# LabPower-power.net
KiCad netlist of a schematic drawn in EAGLE
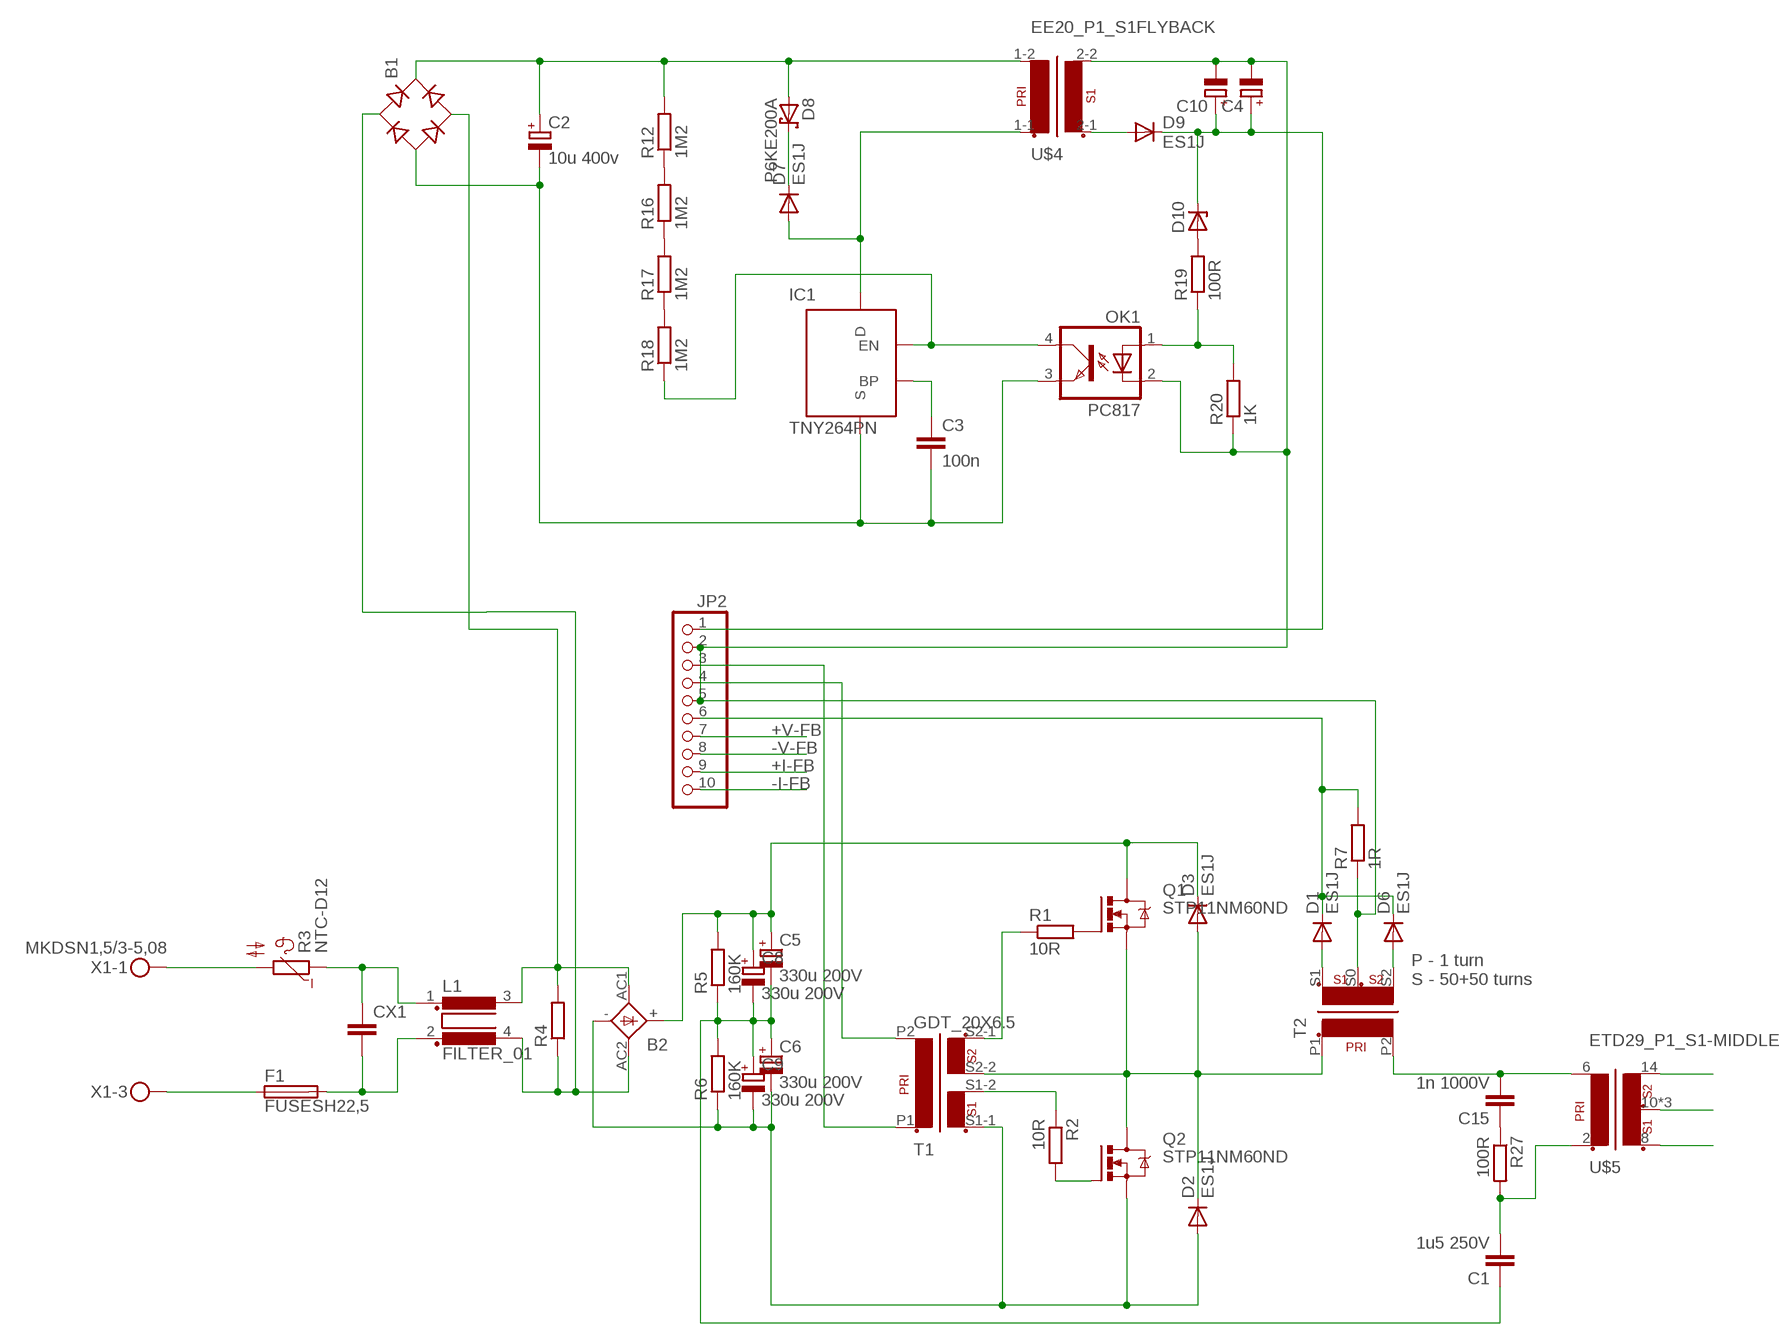
[diagram p0: schematic, sheet 1]
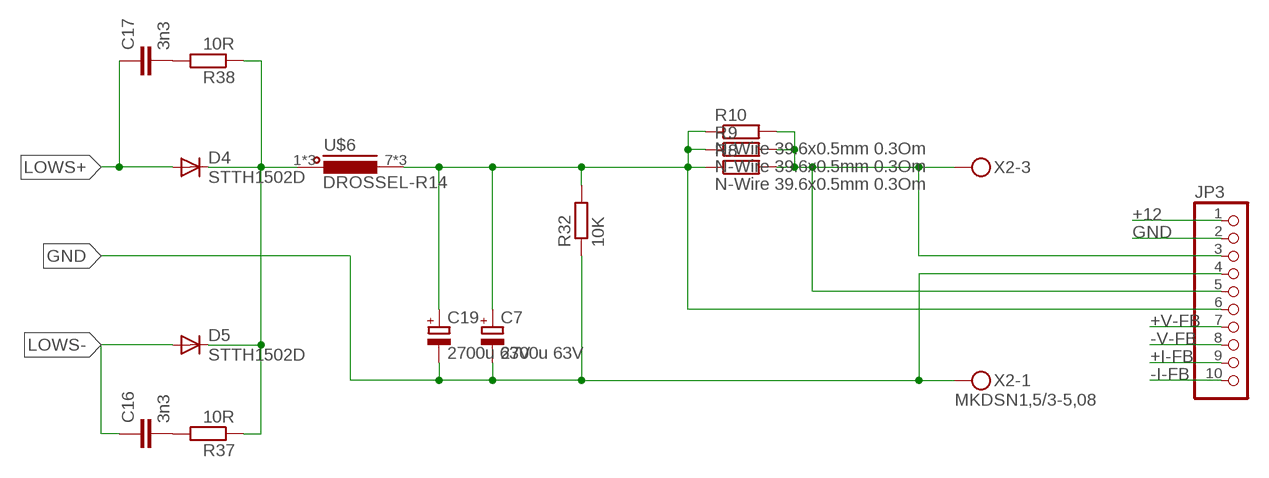
[diagram p1: schematic, sheet 2]

(export (version "E")
  (design (tool "Eeschema 10.0.6"))
  (components
    (comp (ref "B1")
      (value "RB1A")
      (footprint "eagle-import:RB1A")
      (libsource (lib "eagle-import") (part "RB1A"))
    )
    (comp (ref "B2")
      (value "KBL")
      (footprint "eagle-import:KBL")
      (libsource (lib "eagle-import") (part "KBL"))
    )
    (comp (ref "C1")
      (value "1u5 250V")
      (footprint "eagle-import:C225-074X268")
      (libsource (lib "eagle-import") (part "C-EU225-074X268"))
    )
    (comp (ref "C2")
      (value "10u 400v")
      (footprint "eagle-import:E5-13")
      (libsource (lib "eagle-import") (part "CPOL-EUE5-13"))
    )
    (comp (ref "C3")
      (value "100n")
      (footprint "eagle-import:C0805")
      (libsource (lib "eagle-import") (part "C-EUC0805"))
    )
    (comp (ref "C4")
      (value "CPOL-EUE2.5-7")
      (footprint "eagle-import:E2,5-7")
      (libsource (lib "eagle-import") (part "CPOL-EUE2.5-7"))
    )
    (comp (ref "C5")
      (value "330u 200V")
      (footprint "eagle-import:EB22,5D")
      (libsource (lib "eagle-import") (part "CPOL-EUE10-22.5"))
    )
    (comp (ref "C6")
      (value "330u 200V")
      (footprint "eagle-import:EB22,5D")
      (libsource (lib "eagle-import") (part "CPOL-EUE10-22.5"))
    )
    (comp (ref "C8")
      (value "330u 200V")
      (footprint "eagle-import:EB22,5D")
      (libsource (lib "eagle-import") (part "CPOL-EUE10-22.5"))
    )
    (comp (ref "C9")
      (value "330u 200V")
      (footprint "eagle-import:EB22,5D")
      (libsource (lib "eagle-import") (part "CPOL-EUE10-22.5"))
    )
    (comp (ref "C10")
      (value "CPOL-EUE2.5-7")
      (footprint "eagle-import:E2,5-7")
      (libsource (lib "eagle-import") (part "CPOL-EUE2.5-7"))
    )
    (comp (ref "C15")
      (value "1n 1000V")
      (footprint "eagle-import:C050-025X075")
      (libsource (lib "eagle-import") (part "C-EU050-025X075"))
    )
    (comp (ref "CX1")
      (value "CXXC15B8")
      (footprint "eagle-import:XC15B8")
      (libsource (lib "eagle-import") (part "CXXC15B8"))
    )
    (comp (ref "D1")
      (value "ES1J")
      (footprint "eagle-import:DO214AC")
      (libsource (lib "eagle-import") (part "DIODE-DO214AC"))
    )
    (comp (ref "D2")
      (value "ES1J")
      (footprint "eagle-import:DO214AC")
      (libsource (lib "eagle-import") (part "DIODE-DO214AC"))
    )
    (comp (ref "D3")
      (value "ES1J")
      (footprint "eagle-import:DO214AC")
      (libsource (lib "eagle-import") (part "DIODE-DO214AC"))
    )
    (comp (ref "D6")
      (value "ES1J")
      (footprint "eagle-import:DO214AC")
      (libsource (lib "eagle-import") (part "DIODE-DO214AC"))
    )
    (comp (ref "D7")
      (value "ES1J")
      (footprint "eagle-import:DO214AC")
      (libsource (lib "eagle-import") (part "DIODE-DO214AC"))
    )
    (comp (ref "D8")
      (value "P6KE200A")
      (footprint "eagle-import:CB417-15")
      (libsource (lib "eagle-import") (part "P6KEXX"))
    )
    (comp (ref "D9")
      (value "ES1J")
      (footprint "eagle-import:DO214AC")
      (libsource (lib "eagle-import") (part "DIODE-DO214AC"))
    )
    (comp (ref "D10")
      (value "ZENER-DIODEDO41Z10")
      (footprint "eagle-import:DO41Z10")
      (libsource (lib "eagle-import") (part "ZENER-DIODEDO41Z10"))
    )
    (comp (ref "F1")
      (value "FUSESH22,5")
      (footprint "eagle-import:SH22,5")
      (libsource (lib "eagle-import") (part "FUSESH22,5"))
    )
    (comp (ref "IC1")
      (value "TNY264PN")
      (footprint "eagle-import:DIP-8B")
      (libsource (lib "eagle-import") (part "TNY264PN"))
    )
    (comp (ref "JP2")
      (value "PINHD-1X10")
      (footprint "eagle-import:1X10")
      (libsource (lib "eagle-import") (part "PINHD-1X10"))
    )
    (comp (ref "L1")
      (value "FILTER_01")
      (footprint "eagle-import:82721K")
      (libsource (lib "eagle-import") (part "FILTER_01"))
    )
    (comp (ref "OK1")
      (value "PC817")
      (footprint "eagle-import:DIL04")
      (fields (field (name "MPN") "PC817X4J000F"))
      (libsource (lib "eagle-import") (part "PC817"))
    )
    (comp (ref "Q1")
      (value "STP11NM60ND")
      (footprint "eagle-import:TO220BV")
      (libsource (lib "eagle-import") (part "IRF740"))
    )
    (comp (ref "Q2")
      (value "STP11NM60ND")
      (footprint "eagle-import:TO220BV")
      (libsource (lib "eagle-import") (part "IRF740"))
    )
    (comp (ref "R1")
      (value "10R")
      (footprint "eagle-import:R0805")
      (libsource (lib "eagle-import") (part "R-EU_R0805"))
    )
    (comp (ref "R2")
      (value "10R")
      (footprint "eagle-import:R0805")
      (libsource (lib "eagle-import") (part "R-EU_R0805"))
    )
    (comp (ref "R3")
      (value "NTC-D12")
      (footprint "eagle-import:NTC-D12")
      (libsource (lib "eagle-import") (part "NTC-D12"))
    )
    (comp (ref "R4")
      (value "R-EU_0309/10")
      (footprint "eagle-import:0309_10")
      (libsource (lib "eagle-import") (part "R-EU_0309/10"))
    )
    (comp (ref "R5")
      (value "160K")
      (footprint "eagle-import:0207_12")
      (libsource (lib "eagle-import") (part "R-EU_0207/12"))
    )
    (comp (ref "R6")
      (value "160K")
      (footprint "eagle-import:0207_12")
      (libsource (lib "eagle-import") (part "R-EU_0207/12"))
    )
    (comp (ref "R7")
      (value "1R")
      (footprint "eagle-import:R1206")
      (libsource (lib "eagle-import") (part "R-EU_R1206"))
    )
    (comp (ref "R12")
      (value "1M2")
      (footprint "eagle-import:R0805")
      (libsource (lib "eagle-import") (part "R-EU_R0805"))
    )
    (comp (ref "R16")
      (value "1M2")
      (footprint "eagle-import:R0805")
      (libsource (lib "eagle-import") (part "R-EU_R0805"))
    )
    (comp (ref "R17")
      (value "1M2")
      (footprint "eagle-import:R0805")
      (libsource (lib "eagle-import") (part "R-EU_R0805"))
    )
    (comp (ref "R18")
      (value "1M2")
      (footprint "eagle-import:R0805")
      (libsource (lib "eagle-import") (part "R-EU_R0805"))
    )
    (comp (ref "R19")
      (value "100R")
      (footprint "eagle-import:R0805")
      (libsource (lib "eagle-import") (part "R-EU_R0805"))
    )
    (comp (ref "R20")
      (value "1K")
      (footprint "eagle-import:R0805")
      (libsource (lib "eagle-import") (part "R-EU_R0805"))
    )
    (comp (ref "R27")
      (value "100R")
      (footprint "eagle-import:0617_17")
      (libsource (lib "eagle-import") (part "R-EU_0617/17"))
    )
    (comp (ref "T1")
      (value "GDT_20X6.5")
      (footprint "eagle-import:GDT_20X6.5")
      (libsource (lib "eagle-import") (part "GDT_20X6.5"))
    )
    (comp (ref "T2")
      (value "CURRENT")
      (footprint "eagle-import:T_10X6X3")
      (libsource (lib "eagle-import") (part "CURRENT"))
    )
    (comp (ref "U$4")
      (value "EE20_P1_S1FLYBACK")
      (footprint "eagle-import:EE20_P1_S1-REV-4PIN")
      (libsource (lib "eagle-import") (part "EE20_P1_S1FLYBACK"))
    )
    (comp (ref "U$5")
      (value "ETD29_P1_S1-MIDDLE")
      (footprint "eagle-import:ETD29")
      (libsource (lib "eagle-import") (part "ETD29_P1_S1-MIDDLE"))
    )
    (comp (ref "X1")
      (value "MKDSN1,5/3-5,08")
      (footprint "eagle-import:MKDSN1,5_3-5,08")
      (libsource (lib "eagle-import") (part "MKDSN1,5/3-5,08"))
    )
    (comp (ref "C7")
      (value "2700u 63V")
      (footprint "eagle-import:E7,5-18")
      (libsource (lib "eagle-import") (part "CPOL-EUE7.5-18"))
    )
    (comp (ref "C16")
      (value "3n3")
      (footprint "eagle-import:C0805")
      (libsource (lib "eagle-import") (part "C-EUC0805"))
    )
    (comp (ref "C17")
      (value "3n3")
      (footprint "eagle-import:C0805")
      (libsource (lib "eagle-import") (part "C-EUC0805"))
    )
    (comp (ref "C19")
      (value "2700u 63V")
      (footprint "eagle-import:E7,5-18")
      (libsource (lib "eagle-import") (part "CPOL-EUE7.5-18"))
    )
    (comp (ref "D4")
      (value "STTH1502D")
      (footprint "eagle-import:DO220S")
      (libsource (lib "eagle-import") (part "DIODE-DO220S"))
    )
    (comp (ref "D5")
      (value "STTH1502D")
      (footprint "eagle-import:DO220S")
      (libsource (lib "eagle-import") (part "DIODE-DO220S"))
    )
    (comp (ref "JP3")
      (value "PINHD-1X10")
      (footprint "eagle-import:1X10")
      (libsource (lib "eagle-import") (part "PINHD-1X10"))
    )
    (comp (ref "R8")
      (value "N-Wire 39.6x0.5mm 0.3Om")
      (footprint "eagle-import:0207_10")
      (libsource (lib "eagle-import") (part "R-EU_0207/10"))
    )
    (comp (ref "R9")
      (value "N-Wire 39.6x0.5mm 0.3Om")
      (footprint "eagle-import:0207_10")
      (libsource (lib "eagle-import") (part "R-EU_0207/10"))
    )
    (comp (ref "R10")
      (value "N-Wire 39.6x0.5mm 0.3Om")
      (footprint "eagle-import:0207_10")
      (libsource (lib "eagle-import") (part "R-EU_0207/10"))
    )
    (comp (ref "R32")
      (value "10K")
      (footprint "eagle-import:0207_10")
      (libsource (lib "eagle-import") (part "R-EU_0207/10"))
    )
    (comp (ref "R37")
      (value "10R")
      (footprint "eagle-import:R0805")
      (libsource (lib "eagle-import") (part "R-EU_R0805"))
    )
    (comp (ref "R38")
      (value "10R")
      (footprint "eagle-import:R0805")
      (libsource (lib "eagle-import") (part "R-EU_R0805"))
    )
    (comp (ref "U$6")
      (value "DROSSEL-R14")
      (footprint "eagle-import:RM14")
      (libsource (lib "eagle-import") (part "DROSSEL-R14"))
    )
    (comp (ref "X2")
      (value "MKDSN1,5/3-5,08")
      (footprint "eagle-import:MKDSN1,5_3-5,08")
      (libsource (lib "eagle-import") (part "MKDSN1,5/3-5,08"))
    )
  )
  (nets
    (net (code "1") (name "+12") (class "Default")
      (node (ref "C10") (pin "+") (pinfunction "+_+") (pintype "passive"))
      (node (ref "C4") (pin "+") (pinfunction "+_+") (pintype "passive"))
      (node (ref "D10") (pin "C") (pinfunction "C_C") (pintype "passive"))
      (node (ref "D9") (pin "C") (pinfunction "C_C") (pintype "passive"))
      (node (ref "JP2") (pin "1") (pinfunction "1_1") (pintype "passive"))
      (node (ref "JP3") (pin "1") (pinfunction "1_1") (pintype "passive"))
    )
    (net (code "2") (name "+I-FB") (class "Default")
      (node (ref "JP2") (pin "9") (pinfunction "9_9") (pintype "passive"))
      (node (ref "JP3") (pin "9") (pinfunction "9_9") (pintype "passive"))
    )
    (net (code "3") (name "+V-FB") (class "Default")
      (node (ref "JP2") (pin "7") (pinfunction "7_7") (pintype "passive"))
      (node (ref "JP3") (pin "7") (pinfunction "7_7") (pintype "passive"))
    )
    (net (code "4") (name "-I-FB") (class "Default")
      (node (ref "JP2") (pin "10") (pinfunction "10_10") (pintype "passive"))
      (node (ref "JP3") (pin "10") (pinfunction "10_10") (pintype "passive"))
    )
    (net (code "5") (name "-V-FB") (class "Default")
      (node (ref "JP2") (pin "8") (pinfunction "8_8") (pintype "passive"))
      (node (ref "JP3") (pin "8") (pinfunction "8_8") (pintype "passive"))
    )
    (net (code "6") (name "GND") (class "Default")
      (node (ref "C10") (pin "-") (pinfunction "-_-") (pintype "passive"))
      (node (ref "C19") (pin "-") (pinfunction "-_-") (pintype "passive"))
      (node (ref "C4") (pin "-") (pinfunction "-_-") (pintype "passive"))
      (node (ref "C7") (pin "-") (pinfunction "-_-") (pintype "passive"))
      (node (ref "JP2") (pin "2") (pinfunction "2_2") (pintype "passive"))
      (node (ref "JP2") (pin "5") (pinfunction "5_5") (pintype "passive"))
      (node (ref "JP3") (pin "2") (pinfunction "2_2") (pintype "passive"))
      (node (ref "JP3") (pin "4") (pinfunction "4_4") (pintype "passive"))
      (node (ref "OK1") (pin "2") (pinfunction "C_2") (pintype "passive"))
      (node (ref "R20") (pin "1") (pinfunction "1_1") (pintype "passive"))
      (node (ref "R32") (pin "1") (pinfunction "1_1") (pintype "passive"))
      (node (ref "R7") (pin "1") (pinfunction "1_1") (pintype "passive"))
      (node (ref "T2") (pin "S0") (pinfunction "SM_S0") (pintype "passive"))
      (node (ref "U$4") (pin "2-2") (pinfunction "S1-2_2-2") (pintype "passive"))
      (node (ref "U$5") (pin "10") (pinfunction "SM_10") (pintype "passive"))
      (node (ref "U$5") (pin "11") (pinfunction "SM_11") (pintype "passive"))
      (node (ref "U$5") (pin "12") (pinfunction "SM_12") (pintype "passive"))
      (node (ref "X2") (pin "1") (pinfunction "KL_1") (pintype "passive"))
    )
    (net (code "7") (name "LOWS+") (class "Default")
      (node (ref "C17") (pin "1") (pinfunction "1_1") (pintype "passive"))
      (node (ref "D4") (pin "A") (pinfunction "A_A") (pintype "passive"))
      (node (ref "U$5") (pin "14") (pinfunction "S2_14") (pintype "passive"))
    )
    (net (code "8") (name "LOWS-") (class "Default")
      (node (ref "C16") (pin "1") (pinfunction "1_1") (pintype "passive"))
      (node (ref "D5") (pin "A") (pinfunction "A_A") (pintype "passive"))
      (node (ref "U$5") (pin "8") (pinfunction "S1_8") (pintype "passive"))
    )
    (net (code "9") (name "Net-(B2-AC1)") (class "Default")
      (node (ref "B1") (pin "AC1") (pinfunction "AC1_AC1") (pintype "passive"))
      (node (ref "B2") (pin "AC2") (pinfunction "AC1_AC2") (pintype "passive"))
      (node (ref "L1") (pin "4") (pinfunction "4_4") (pintype "passive"))
      (node (ref "R4") (pin "1") (pinfunction "1_1") (pintype "passive"))
    )
    (net (code "10") (name "Net-(B2-AC2)") (class "Default")
      (node (ref "B1") (pin "AC2") (pinfunction "AC2_AC2") (pintype "passive"))
      (node (ref "B2") (pin "AC1") (pinfunction "AC2_AC1") (pintype "passive"))
      (node (ref "L1") (pin "3") (pinfunction "2_3") (pintype "passive"))
      (node (ref "R4") (pin "2") (pinfunction "2_2") (pintype "passive"))
    )
    (net (code "11") (name "Net-(B2-Pad+)") (class "Default")
      (node (ref "B2") (pin "+") (pinfunction "+_+") (pintype "passive"))
      (node (ref "C5") (pin "+") (pinfunction "+_+") (pintype "passive"))
      (node (ref "C8") (pin "+") (pinfunction "+_+") (pintype "passive"))
      (node (ref "D3") (pin "C") (pinfunction "C_C") (pintype "passive"))
      (node (ref "Q1") (pin "D") (pinfunction "D_D") (pintype "passive"))
      (node (ref "R5") (pin "2") (pinfunction "2_2") (pintype "passive"))
    )
    (net (code "12") (name "Net-(B2-Pad-)") (class "Default")
      (node (ref "B2") (pin "-") (pinfunction "-_-") (pintype "passive"))
      (node (ref "C6") (pin "-") (pinfunction "-_-") (pintype "passive"))
      (node (ref "C9") (pin "-") (pinfunction "-_-") (pintype "passive"))
      (node (ref "D2") (pin "A") (pinfunction "A_A") (pintype "passive"))
      (node (ref "Q2") (pin "S") (pinfunction "S_S") (pintype "passive"))
      (node (ref "R6") (pin "1") (pinfunction "1_1") (pintype "passive"))
      (node (ref "T1") (pin "S1-1") (pinfunction "S1-1_S1-1") (pintype "passive"))
    )
    (net (code "13") (name "Net-(C1-Pad1)") (class "Default")
      (node (ref "C1") (pin "1") (pinfunction "1_1") (pintype "passive"))
      (node (ref "C5") (pin "-") (pinfunction "-_-") (pintype "passive"))
      (node (ref "C6") (pin "+") (pinfunction "+_+") (pintype "passive"))
      (node (ref "C8") (pin "-") (pinfunction "-_-") (pintype "passive"))
      (node (ref "C9") (pin "+") (pinfunction "+_+") (pintype "passive"))
      (node (ref "R5") (pin "1") (pinfunction "1_1") (pintype "passive"))
      (node (ref "R6") (pin "2") (pinfunction "2_2") (pintype "passive"))
    )
    (net (code "14") (name "Net-(C15-Pad1)") (class "Default")
      (node (ref "C15") (pin "1") (pinfunction "1_1") (pintype "passive"))
      (node (ref "R27") (pin "1") (pinfunction "1_1") (pintype "passive"))
    )
    (net (code "15") (name "Net-(C16-Pad2)") (class "Default")
      (node (ref "C16") (pin "2") (pinfunction "2_2") (pintype "passive"))
      (node (ref "R37") (pin "2") (pinfunction "2_2") (pintype "passive"))
    )
    (net (code "16") (name "Net-(C17-Pad2)") (class "Default")
      (node (ref "C17") (pin "2") (pinfunction "2_2") (pintype "passive"))
      (node (ref "R38") (pin "2") (pinfunction "2_2") (pintype "passive"))
    )
    (net (code "17") (name "Net-(C19-Pad+)") (class "Default")
      (node (ref "C19") (pin "+") (pinfunction "+_+") (pintype "passive"))
      (node (ref "C7") (pin "+") (pinfunction "+_+") (pintype "passive"))
      (node (ref "JP3") (pin "6") (pinfunction "6_6") (pintype "passive"))
      (node (ref "R10") (pin "1") (pinfunction "1_1") (pintype "passive"))
      (node (ref "R32") (pin "2") (pinfunction "2_2") (pintype "passive"))
      (node (ref "R8") (pin "1") (pinfunction "1_1") (pintype "passive"))
      (node (ref "R9") (pin "1") (pinfunction "1_1") (pintype "passive"))
      (node (ref "U$6") (pin "7") (pinfunction "2_7") (pintype "passive"))
      (node (ref "U$6") (pin "8") (pinfunction "2_8") (pintype "passive"))
      (node (ref "U$6") (pin "9") (pinfunction "2_9") (pintype "passive"))
    )
    (net (code "18") (name "Net-(CX1-Pad1)") (class "Default")
      (node (ref "CX1") (pin "1") (pinfunction "1_1") (pintype "passive"))
      (node (ref "L1") (pin "1") (pinfunction "1_1") (pintype "passive"))
      (node (ref "R3") (pin "1") (pinfunction "1_1") (pintype "passive"))
    )
    (net (code "19") (name "Net-(D1-PadA)") (class "Default")
      (node (ref "D1") (pin "A") (pinfunction "A_A") (pintype "passive"))
      (node (ref "T2") (pin "S1") (pinfunction "S1_S1") (pintype "passive"))
    )
    (net (code "20") (name "Net-(D1-PadC)") (class "Default")
      (node (ref "D1") (pin "C") (pinfunction "C_C") (pintype "passive"))
      (node (ref "D6") (pin "C") (pinfunction "C_C") (pintype "passive"))
      (node (ref "JP2") (pin "6") (pinfunction "6_6") (pintype "passive"))
      (node (ref "R7") (pin "2") (pinfunction "2_2") (pintype "passive"))
    )
    (net (code "21") (name "Net-(D4-PadC)") (class "Default")
      (node (ref "D4") (pin "C") (pinfunction "C_C") (pintype "passive"))
      (node (ref "D5") (pin "C") (pinfunction "C_C") (pintype "passive"))
      (node (ref "R37") (pin "1") (pinfunction "1_1") (pintype "passive"))
      (node (ref "R38") (pin "1") (pinfunction "1_1") (pintype "passive"))
      (node (ref "U$6") (pin "1") (pinfunction "1_1") (pintype "passive"))
      (node (ref "U$6") (pin "2") (pinfunction "1_2") (pintype "passive"))
      (node (ref "U$6") (pin "3") (pinfunction "1_3") (pintype "passive"))
    )
    (net (code "22") (name "Net-(D6-PadA)") (class "Default")
      (node (ref "D6") (pin "A") (pinfunction "A_A") (pintype "passive"))
      (node (ref "T2") (pin "S2") (pinfunction "S2_S2") (pintype "passive"))
    )
    (net (code "23") (name "Net-(D7-PadC)") (class "Default")
      (node (ref "D7") (pin "C") (pinfunction "C_C") (pintype "passive"))
      (node (ref "D8") (pin "C") (pinfunction "C_C") (pintype "passive"))
    )
    (net (code "24") (name "Net-(D10-PadA)") (class "Default")
      (node (ref "D10") (pin "A") (pinfunction "A_A") (pintype "passive"))
      (node (ref "R19") (pin "2") (pinfunction "2_2") (pintype "passive"))
    )
    (net (code "25") (name "Net-(IC1-BP)") (class "Default")
      (node (ref "C3") (pin "1") (pinfunction "1_1") (pintype "passive"))
      (node (ref "IC1") (pin "1") (pinfunction "BP_1") (pintype "input"))
    )
    (net (code "26") (name "Net-(IC1-D)") (class "Default")
      (node (ref "D7") (pin "A") (pinfunction "A_A") (pintype "passive"))
      (node (ref "IC1") (pin "5") (pinfunction "D_5") (pintype "input"))
      (node (ref "U$4") (pin "1-1") (pinfunction "P1-1_1-1") (pintype "passive"))
    )
    (net (code "27") (name "Net-(IC1-EN)") (class "Default")
      (node (ref "IC1") (pin "4") (pinfunction "EN_4") (pintype "input"))
      (node (ref "OK1") (pin "4") (pinfunction "COL_4") (pintype "passive"))
      (node (ref "R18") (pin "1") (pinfunction "1_1") (pintype "passive"))
    )
    (net (code "28") (name "Net-(L1-3)") (class "Default")
      (node (ref "CX1") (pin "2") (pinfunction "2_2") (pintype "passive"))
      (node (ref "F1") (pin "2") (pinfunction "2_2") (pintype "passive"))
      (node (ref "L1") (pin "2") (pinfunction "3_2") (pintype "passive"))
    )
    (net (code "29") (name "Net-(OK1-A)") (class "Default")
      (node (ref "OK1") (pin "1") (pinfunction "A_1") (pintype "passive"))
      (node (ref "R19") (pin "1") (pinfunction "1_1") (pintype "passive"))
      (node (ref "R20") (pin "2") (pinfunction "2_2") (pintype "passive"))
    )
    (net (code "30") (name "Net-(OK1-EMIT)") (class "Default")
      (node (ref "B1") (pin "-") (pinfunction "-_-") (pintype "passive"))
      (node (ref "C2") (pin "-") (pinfunction "-_-") (pintype "passive"))
      (node (ref "C3") (pin "2") (pinfunction "2_2") (pintype "passive"))
      (node (ref "IC1") (pin "2") (pinfunction "S_2") (pintype "input"))
      (node (ref "IC1") (pin "3") (pinfunction "S_3") (pintype "input"))
      (node (ref "IC1") (pin "7") (pinfunction "S_7") (pintype "input"))
      (node (ref "IC1") (pin "8") (pinfunction "S_8") (pintype "input"))
      (node (ref "OK1") (pin "3") (pinfunction "EMIT_3") (pintype "passive"))
    )
    (net (code "31") (name "Net-(Q1-PadG)") (class "Default")
      (node (ref "Q1") (pin "G") (pinfunction "G_G") (pintype "passive"))
      (node (ref "R1") (pin "2") (pinfunction "2_2") (pintype "passive"))
    )
    (net (code "32") (name "Net-(Q2-PadG)") (class "Default")
      (node (ref "Q2") (pin "G") (pinfunction "G_G") (pintype "passive"))
      (node (ref "R2") (pin "2") (pinfunction "2_2") (pintype "passive"))
    )
    (net (code "33") (name "Net-(R1-Pad1)") (class "Default")
      (node (ref "R1") (pin "1") (pinfunction "1_1") (pintype "passive"))
      (node (ref "T1") (pin "S2-1") (pinfunction "S2-1_S2-1") (pintype "passive"))
    )
    (net (code "34") (name "Net-(R2-Pad1)") (class "Default")
      (node (ref "R2") (pin "1") (pinfunction "1_1") (pintype "passive"))
      (node (ref "T1") (pin "S1-2") (pinfunction "S1-2_S1-2") (pintype "passive"))
    )
    (net (code "35") (name "Net-(R12-Pad1)") (class "Default")
      (node (ref "R12") (pin "1") (pinfunction "1_1") (pintype "passive"))
      (node (ref "R16") (pin "2") (pinfunction "2_2") (pintype "passive"))
    )
    (net (code "36") (name "Net-(R16-Pad1)") (class "Default")
      (node (ref "R16") (pin "1") (pinfunction "1_1") (pintype "passive"))
      (node (ref "R17") (pin "2") (pinfunction "2_2") (pintype "passive"))
    )
    (net (code "37") (name "Net-(R17-Pad1)") (class "Default")
      (node (ref "R17") (pin "1") (pinfunction "1_1") (pintype "passive"))
      (node (ref "R18") (pin "2") (pinfunction "2_2") (pintype "passive"))
    )
    (net (code "38") (name "Net-(T1-P1-1)") (class "Default")
      (node (ref "JP2") (pin "3") (pinfunction "3_3") (pintype "passive"))
      (node (ref "T1") (pin "P1") (pinfunction "P1-1_P1") (pintype "passive"))
    )
    (net (code "39") (name "Net-(T1-P1-2)") (class "Default")
      (node (ref "JP2") (pin "4") (pinfunction "4_4") (pintype "passive"))
      (node (ref "T1") (pin "P2") (pinfunction "P1-2_P2") (pintype "passive"))
    )
    (net (code "40") (name "Net-(T2-P1-1)") (class "Default")
      (node (ref "D2") (pin "C") (pinfunction "C_C") (pintype "passive"))
      (node (ref "D3") (pin "A") (pinfunction "A_A") (pintype "passive"))
      (node (ref "Q1") (pin "S") (pinfunction "S_S") (pintype "passive"))
      (node (ref "Q2") (pin "D") (pinfunction "D_D") (pintype "passive"))
      (node (ref "T1") (pin "S2-2") (pinfunction "S2-2_S2-2") (pintype "passive"))
      (node (ref "T2") (pin "P1") (pinfunction "P1-1_P1") (pintype "passive"))
    )
    (net (code "41") (name "Net-(T2-P1-2)") (class "Default")
      (node (ref "C15") (pin "2") (pinfunction "2_2") (pintype "passive"))
      (node (ref "T2") (pin "P2") (pinfunction "P1-2_P2") (pintype "passive"))
      (node (ref "U$5") (pin "6") (pinfunction "P1-2_6") (pintype "passive"))
    )
    (net (code "42") (name "Net-(U$4-P1-2)") (class "Default")
      (node (ref "B1") (pin "+") (pinfunction "+_+") (pintype "passive"))
      (node (ref "C2") (pin "+") (pinfunction "+_+") (pintype "passive"))
      (node (ref "D8") (pin "A") (pinfunction "A_A") (pintype "passive"))
      (node (ref "R12") (pin "2") (pinfunction "2_2") (pintype "passive"))
      (node (ref "U$4") (pin "1-2") (pinfunction "P1-2_1-2") (pintype "passive"))
    )
    (net (code "43") (name "Net-(U$4-S1-1)") (class "Default")
      (node (ref "D9") (pin "A") (pinfunction "A_A") (pintype "passive"))
      (node (ref "U$4") (pin "2-1") (pinfunction "S1-1_2-1") (pintype "passive"))
    )
    (net (code "44") (name "Net-(U$5-P1-1)") (class "Default")
      (node (ref "C1") (pin "2") (pinfunction "2_2") (pintype "passive"))
      (node (ref "R27") (pin "2") (pinfunction "2_2") (pintype "passive"))
      (node (ref "U$5") (pin "2") (pinfunction "P1-1_2") (pintype "passive"))
    )
    (net (code "45") (name "Net-(X1A-KL)") (class "Default")
      (node (ref "R3") (pin "2") (pinfunction "2_2") (pintype "passive"))
      (node (ref "X1") (pin "1") (pinfunction "KL_1") (pintype "passive"))
    )
    (net (code "46") (name "Net-(X1C-KL)") (class "Default")
      (node (ref "F1") (pin "1") (pinfunction "1_1") (pintype "passive"))
      (node (ref "X1") (pin "3") (pinfunction "KL_3") (pintype "passive"))
    )
    (net (code "47") (name "Net-(X2C-KL)") (class "Default")
      (node (ref "JP3") (pin "3") (pinfunction "3_3") (pintype "passive"))
      (node (ref "JP3") (pin "5") (pinfunction "5_5") (pintype "passive"))
      (node (ref "R10") (pin "2") (pinfunction "2_2") (pintype "passive"))
      (node (ref "R8") (pin "2") (pinfunction "2_2") (pintype "passive"))
      (node (ref "R9") (pin "2") (pinfunction "2_2") (pintype "passive"))
      (node (ref "X2") (pin "3") (pinfunction "KL_3") (pintype "passive"))
    )
  )
)
